# ScaledModelBoard.net
KiCad netlist of a schematic drawn in Altium Designer
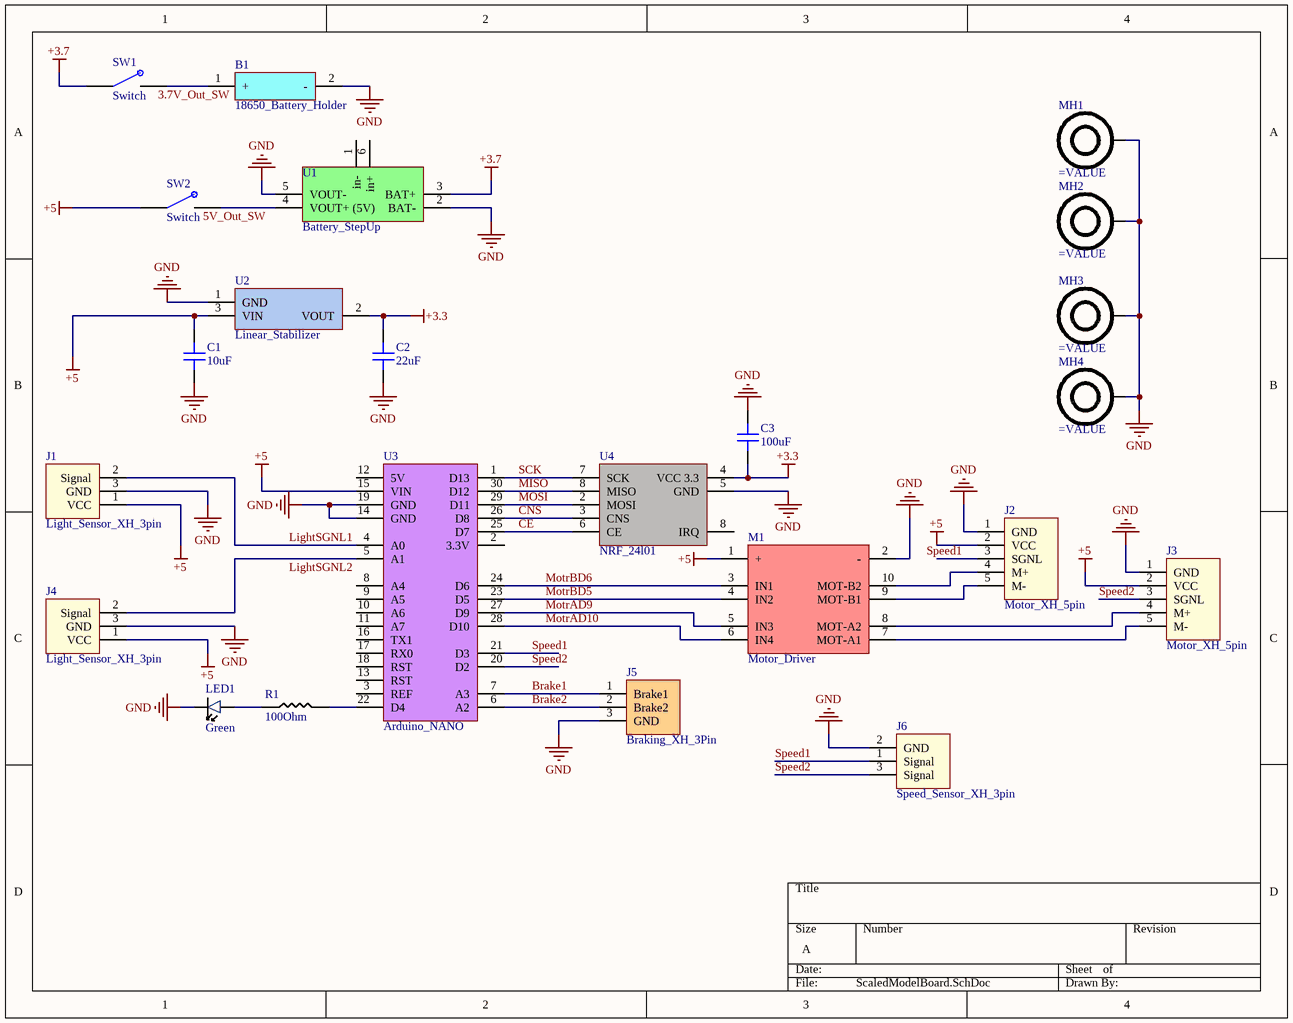
[diagram p0: ScaledModelBoard.SchDoc]

(export (version "E")
  (design (tool "Eeschema 10.0.6"))
  (components
    (comp (ref "B1")
      (value "18650_Battery_Holder")
      (footprint "18650")
      (libsource (lib "Schlib1") (part "18650_Battery_Holder"))
    )
    (comp (ref "C1")
      (value "10uF")
      (footprint "CAP 1206")
      (description "SMT Capacitor")
      (libsource (lib "Schlib1") (part "Capacitor"))
    )
    (comp (ref "C2")
      (value "22uF")
      (footprint "CAP 1206")
      (description "SMT Capacitor")
      (libsource (lib "Schlib1") (part "Capacitor"))
    )
    (comp (ref "C3")
      (value "100uF")
      (footprint "CAP 1206")
      (description "SMT Capacitor")
      (libsource (lib "Schlib1") (part "Capacitor"))
    )
    (comp (ref "J1")
      (value "Light_Sensor_XH_3pin")
      (footprint "JST XH B3B-XH-A")
      (libsource (lib "Schlib1") (part "Light_Sensor_XH_3pin"))
    )
    (comp (ref "J2")
      (value "Motor_XH_5pin")
      (footprint "JST XH B5B-XH-A")
      (libsource (lib "Schlib1") (part "Motor_XH_5pin"))
    )
    (comp (ref "J3")
      (value "Motor_XH_5pin")
      (footprint "JST XH B5B-XH-A")
      (libsource (lib "Schlib1") (part "Motor_XH_5pin"))
    )
    (comp (ref "J4")
      (value "Light_Sensor_XH_3pin")
      (footprint "JST XH B3B-XH-A")
      (libsource (lib "Schlib1") (part "Light_Sensor_XH_3pin"))
    )
    (comp (ref "J5")
      (value "Braking_XH_3Pin")
      (footprint "JST XH B3B-XH-A")
      (libsource (lib "Schlib1") (part "Braking_XH_3Pin"))
    )
    (comp (ref "J6")
      (value "Speed_Sensor_XH_3pin")
      (footprint "JST XH B3B-XH-A")
      (libsource (lib "Schlib1") (part "Speed_Sensor_XH_3pin"))
    )
    (comp (ref "LED1")
      (value "Green")
      (footprint "LED_0603")
      (description "LIGHT EMITTING DIODES (LED) GREEN 520~535NM 112~258MCD@20MA TOP VIEW 0603 ROHS")
      (fields (field (name "MFR PART #") "19-217/GHC-YR1S2/3T") (field (name "LCSC PART#") "C72043"))
      (libsource (lib "Schlib1") (part "LED_GREEN_0603"))
    )
    (comp (ref "M1")
      (value "Motor_Driver")
      (footprint "Driver")
      (libsource (lib "Schlib1") (part "Motor_Driver"))
    )
    (comp (ref "MH1") (value "~") (footprint "SCREW_M3.0") (libsource (lib "Schlib1") (part "SCREW")))
    (comp (ref "MH2") (value "~") (footprint "SCREW_M3.0") (libsource (lib "Schlib1") (part "SCREW")))
    (comp (ref "MH3") (value "~") (footprint "SCREW_M3.0") (libsource (lib "Schlib1") (part "SCREW")))
    (comp (ref "MH4") (value "~") (footprint "SCREW_M3.0") (libsource (lib "Schlib1") (part "SCREW")))
    (comp (ref "R1")
      (value "100Ohm")
      (footprint "RES 0603")
      (description "100Ω ±1% 0.25W ±100ppm/℃ 1206 Chip Resistor - Surface Mount RoHS")
      (fields (field (name "LCSC PART#") "C17901") (field (name "MFR PART #") "1206W4F1000T5E"))
      (libsource (lib "ScaledModelBoard") (part "R_100Ohm_1206"))
    )
    (comp (ref "SW1") (value "Switch") (footprint "Switch") (libsource (lib "Schlib1") (part "Switch")))
    (comp (ref "SW2") (value "Switch") (footprint "Switch") (libsource (lib "Schlib1") (part "Switch")))
    (comp (ref "U1")
      (value "Battery_StepUp")
      (footprint "DC/DC")
      (libsource (lib "Schlib1") (part "Battery_StepUp"))
    )
    (comp (ref "U2")
      (value "Linear_Stabilizer")
      (footprint "TO-220")
      (libsource (lib "Schlib1") (part "Linear_Stabilizer"))
    )
    (comp (ref "U3")
      (value "Arduino_NANO")
      (footprint "MODULE_ABX00028")
      (libsource (lib "Schlib1") (part "Arduino_NANO"))
    )
    (comp (ref "U4")
      (value "NRF_24l01")
      (footprint "NRF24L01")
      (libsource (lib "Schlib1") (part "NRF_24l01"))
    )
  )
  (nets
    (net (code "1") (name "+3.3") (class "Default")
      (node (ref "C2") (pin "2") (pinfunction "2_2") (pintype "passive"))
      (node (ref "C3") (pin "1") (pinfunction "1_1") (pintype "passive"))
      (node (ref "U2") (pin "2") (pinfunction "VOUT_2") (pintype "passive"))
      (node (ref "U4") (pin "4") (pinfunction "VCC_3.3_4") (pintype "passive"))
    )
    (net (code "2") (name "+3.7") (class "Default")
      (node (ref "SW1") (pin "1") (pinfunction "1_1") (pintype "passive"))
      (node (ref "U1") (pin "3") (pinfunction "BAT+_3") (pintype "passive"))
    )
    (net (code "3") (name "+5") (class "Default")
      (node (ref "C1") (pin "2") (pinfunction "2_2") (pintype "passive"))
      (node (ref "J1") (pin "1") (pinfunction "VCC_1") (pintype "passive"))
      (node (ref "J2") (pin "2") (pinfunction "VCC_2") (pintype "passive"))
      (node (ref "J3") (pin "2") (pinfunction "VCC_2") (pintype "passive"))
      (node (ref "J4") (pin "1") (pinfunction "VCC_1") (pintype "passive"))
      (node (ref "M1") (pin "1") (pinfunction "+_1") (pintype "passive"))
      (node (ref "SW2") (pin "1") (pinfunction "1_1") (pintype "passive"))
      (node (ref "U2") (pin "3") (pinfunction "VIN_3") (pintype "passive"))
      (node (ref "U3") (pin "15") (pinfunction "VIN_15") (pintype "passive"))
    )
    (net (code "4") (name "/3.7V_Out_SW") (class "Default")
      (node (ref "B1") (pin "1") (pinfunction "+_1") (pintype "passive"))
      (node (ref "SW1") (pin "2") (pinfunction "2_2") (pintype "passive"))
    )
    (net (code "5") (name "/5V_Out_SW") (class "Default")
      (node (ref "SW2") (pin "2") (pinfunction "2_2") (pintype "passive"))
      (node (ref "U1") (pin "4") (pinfunction "VOUT+_(5V)_4") (pintype "passive"))
    )
    (net (code "6") (name "/Brake1") (class "Default")
      (node (ref "J5") (pin "1") (pinfunction "Brake1_1") (pintype "passive"))
      (node (ref "U3") (pin "7") (pinfunction "A3_7") (pintype "passive"))
    )
    (net (code "7") (name "/Brake2") (class "Default")
      (node (ref "J5") (pin "2") (pinfunction "Brake2_2") (pintype "passive"))
      (node (ref "U3") (pin "6") (pinfunction "A2_6") (pintype "passive"))
    )
    (net (code "8") (name "/CE") (class "Default")
      (node (ref "U3") (pin "25") (pinfunction "D7_25") (pintype "passive"))
      (node (ref "U4") (pin "6") (pinfunction "CE_6") (pintype "passive"))
    )
    (net (code "9") (name "/CNS") (class "Default")
      (node (ref "U3") (pin "26") (pinfunction "D8_26") (pintype "passive"))
      (node (ref "U4") (pin "3") (pinfunction "CNS_3") (pintype "passive"))
    )
    (net (code "10") (name "/LightSGNL1") (class "Default")
      (node (ref "J1") (pin "2") (pinfunction "Signal_2") (pintype "passive"))
      (node (ref "U3") (pin "4") (pinfunction "A0_4") (pintype "passive"))
    )
    (net (code "11") (name "/LightSGNL2") (class "Default")
      (node (ref "J4") (pin "2") (pinfunction "Signal_2") (pintype "passive"))
      (node (ref "U3") (pin "5") (pinfunction "A1_5") (pintype "passive"))
    )
    (net (code "12") (name "/MISO") (class "Default")
      (node (ref "U3") (pin "30") (pinfunction "D12_30") (pintype "passive"))
      (node (ref "U4") (pin "8") (pinfunction "MISO_8") (pintype "passive"))
    )
    (net (code "13") (name "/MOSI") (class "Default")
      (node (ref "U3") (pin "29") (pinfunction "D11_29") (pintype "passive"))
      (node (ref "U4") (pin "2") (pinfunction "MOSI_2") (pintype "passive"))
    )
    (net (code "14") (name "/MotrAD9") (class "Default")
      (node (ref "M1") (pin "5") (pinfunction "IN3_5") (pintype "passive"))
      (node (ref "U3") (pin "27") (pinfunction "D9_27") (pintype "passive"))
    )
    (net (code "15") (name "/MotrAD10") (class "Default")
      (node (ref "M1") (pin "6") (pinfunction "IN4_6") (pintype "passive"))
      (node (ref "U3") (pin "28") (pinfunction "D10_28") (pintype "passive"))
    )
    (net (code "16") (name "/MotrBD5") (class "Default")
      (node (ref "M1") (pin "4") (pinfunction "IN2_4") (pintype "passive"))
      (node (ref "U3") (pin "23") (pinfunction "D5_23") (pintype "passive"))
    )
    (net (code "17") (name "/MotrBD6") (class "Default")
      (node (ref "M1") (pin "3") (pinfunction "IN1_3") (pintype "passive"))
      (node (ref "U3") (pin "24") (pinfunction "D6_24") (pintype "passive"))
    )
    (net (code "18") (name "/SCK") (class "Default")
      (node (ref "U3") (pin "1") (pinfunction "D13_1") (pintype "passive"))
      (node (ref "U4") (pin "7") (pinfunction "SCK_7") (pintype "passive"))
    )
    (net (code "19") (name "/Speed1") (class "Default")
      (node (ref "J2") (pin "3") (pinfunction "SGNL_3") (pintype "passive"))
      (node (ref "J6") (pin "1") (pinfunction "Signal_1") (pintype "passive"))
      (node (ref "U3") (pin "21") (pinfunction "D3_21") (pintype "passive"))
    )
    (net (code "20") (name "/Speed2") (class "Default")
      (node (ref "J3") (pin "3") (pinfunction "SGNL_3") (pintype "passive"))
      (node (ref "J6") (pin "3") (pinfunction "Signal_3") (pintype "passive"))
      (node (ref "U3") (pin "20") (pinfunction "D2_20") (pintype "passive"))
    )
    (net (code "21") (name "GND") (class "Default")
      (node (ref "B1") (pin "2") (pinfunction "-_2") (pintype "passive"))
      (node (ref "C1") (pin "1") (pinfunction "1_1") (pintype "passive"))
      (node (ref "C2") (pin "1") (pinfunction "1_1") (pintype "passive"))
      (node (ref "C3") (pin "2") (pinfunction "2_2") (pintype "passive"))
      (node (ref "J1") (pin "3") (pinfunction "GND_3") (pintype "passive"))
      (node (ref "J2") (pin "1") (pinfunction "GND_1") (pintype "passive"))
      (node (ref "J3") (pin "1") (pinfunction "GND_1") (pintype "passive"))
      (node (ref "J4") (pin "3") (pinfunction "GND_3") (pintype "passive"))
      (node (ref "J5") (pin "3") (pinfunction "GND_3") (pintype "passive"))
      (node (ref "J6") (pin "2") (pinfunction "GND_2") (pintype "passive"))
      (node (ref "LED1") (pin "2") (pinfunction "2_2") (pintype "passive"))
      (node (ref "M1") (pin "2") (pinfunction "-_2") (pintype "passive"))
      (node (ref "MH1") (pin "1") (pinfunction "1_1") (pintype "passive"))
      (node (ref "MH2") (pin "1") (pinfunction "1_1") (pintype "passive"))
      (node (ref "MH3") (pin "1") (pinfunction "1_1") (pintype "passive"))
      (node (ref "MH4") (pin "1") (pinfunction "1_1") (pintype "passive"))
      (node (ref "U1") (pin "2") (pinfunction "BAT-_2") (pintype "passive"))
      (node (ref "U1") (pin "5") (pinfunction "VOUT-_5") (pintype "passive"))
      (node (ref "U2") (pin "1") (pinfunction "GND_1") (pintype "passive"))
      (node (ref "U3") (pin "14") (pinfunction "GND_14") (pintype "passive"))
      (node (ref "U3") (pin "19") (pinfunction "GND_19") (pintype "passive"))
      (node (ref "U4") (pin "5") (pinfunction "GND_5") (pintype "passive"))
    )
    (net (code "22") (name "Net-(J2-M+)") (class "Default")
      (node (ref "J2") (pin "4") (pinfunction "M+_4") (pintype "passive"))
      (node (ref "M1") (pin "10") (pinfunction "MOT-B2_10") (pintype "passive"))
    )
    (net (code "23") (name "Net-(J2-M-)") (class "Default")
      (node (ref "J2") (pin "5") (pinfunction "M-_5") (pintype "passive"))
      (node (ref "M1") (pin "9") (pinfunction "MOT-B1_9") (pintype "passive"))
    )
    (net (code "24") (name "Net-(J3-M+)") (class "Default")
      (node (ref "J3") (pin "4") (pinfunction "M+_4") (pintype "passive"))
      (node (ref "M1") (pin "8") (pinfunction "MOT-A2_8") (pintype "passive"))
    )
    (net (code "25") (name "Net-(J3-M-)") (class "Default")
      (node (ref "J3") (pin "5") (pinfunction "M-_5") (pintype "passive"))
      (node (ref "M1") (pin "7") (pinfunction "MOT-A1_7") (pintype "passive"))
    )
    (net (code "26") (name "Net-(LED1-Pad1)") (class "Default")
      (node (ref "LED1") (pin "1") (pinfunction "1_1") (pintype "passive"))
      (node (ref "R1") (pin "1") (pinfunction "1_1") (pintype "passive"))
    )
    (net (code "27") (name "Net-(U3-D4)") (class "Default")
      (node (ref "R1") (pin "2") (pinfunction "2_2") (pintype "passive"))
      (node (ref "U3") (pin "22") (pinfunction "D4_22") (pintype "passive"))
    )
    (net (code "28") (name "unconnected-(U1-in+-Pad6)") (class "Default")
      (node (ref "U1") (pin "6") (pinfunction "in+_6") (pintype "passive"))
    )
    (net (code "29") (name "unconnected-(U1-in--Pad1)") (class "Default")
      (node (ref "U1") (pin "1") (pinfunction "in-_1") (pintype "passive"))
    )
    (net (code "30") (name "unconnected-(U3-3.3V-Pad2)") (class "Default")
      (node (ref "U3") (pin "2") (pinfunction "3.3V_2") (pintype "passive"))
    )
    (net (code "31") (name "unconnected-(U3-5V-Pad12)") (class "Default")
      (node (ref "U3") (pin "12") (pinfunction "5V_12") (pintype "passive"))
    )
    (net (code "32") (name "unconnected-(U3-A4-Pad8)") (class "Default")
      (node (ref "U3") (pin "8") (pinfunction "A4_8") (pintype "passive"))
    )
    (net (code "33") (name "unconnected-(U3-A5-Pad9)") (class "Default")
      (node (ref "U3") (pin "9") (pinfunction "A5_9") (pintype "passive"))
    )
    (net (code "34") (name "unconnected-(U3-A6-Pad10)") (class "Default")
      (node (ref "U3") (pin "10") (pinfunction "A6_10") (pintype "passive"))
    )
    (net (code "35") (name "unconnected-(U3-A7-Pad11)") (class "Default")
      (node (ref "U3") (pin "11") (pinfunction "A7_11") (pintype "passive"))
    )
    (net (code "36") (name "unconnected-(U3-REF-Pad3)") (class "Default")
      (node (ref "U3") (pin "3") (pinfunction "REF_3") (pintype "passive"))
    )
    (net (code "37") (name "unconnected-(U3-RST-Pad13)") (class "Default")
      (node (ref "U3") (pin "13") (pinfunction "RST_13") (pintype "passive"))
    )
    (net (code "38") (name "unconnected-(U3-RST-Pad18)") (class "Default")
      (node (ref "U3") (pin "18") (pinfunction "RST_18") (pintype "passive"))
    )
    (net (code "39") (name "unconnected-(U3-RX0-Pad17)") (class "Default")
      (node (ref "U3") (pin "17") (pinfunction "RX0_17") (pintype "passive"))
    )
    (net (code "40") (name "unconnected-(U3-TX1-Pad16)") (class "Default")
      (node (ref "U3") (pin "16") (pinfunction "TX1_16") (pintype "passive"))
    )
    (net (code "41") (name "unconnected-(U4-IRQ-Pad8)") (class "Default")
      (node (ref "U4") (pin "8") (pinfunction "IRQ_8") (pintype "passive"))
    )
  )
)
